# 300_PCB1.net
KiCad netlist of a schematic drawn in Altium Designer
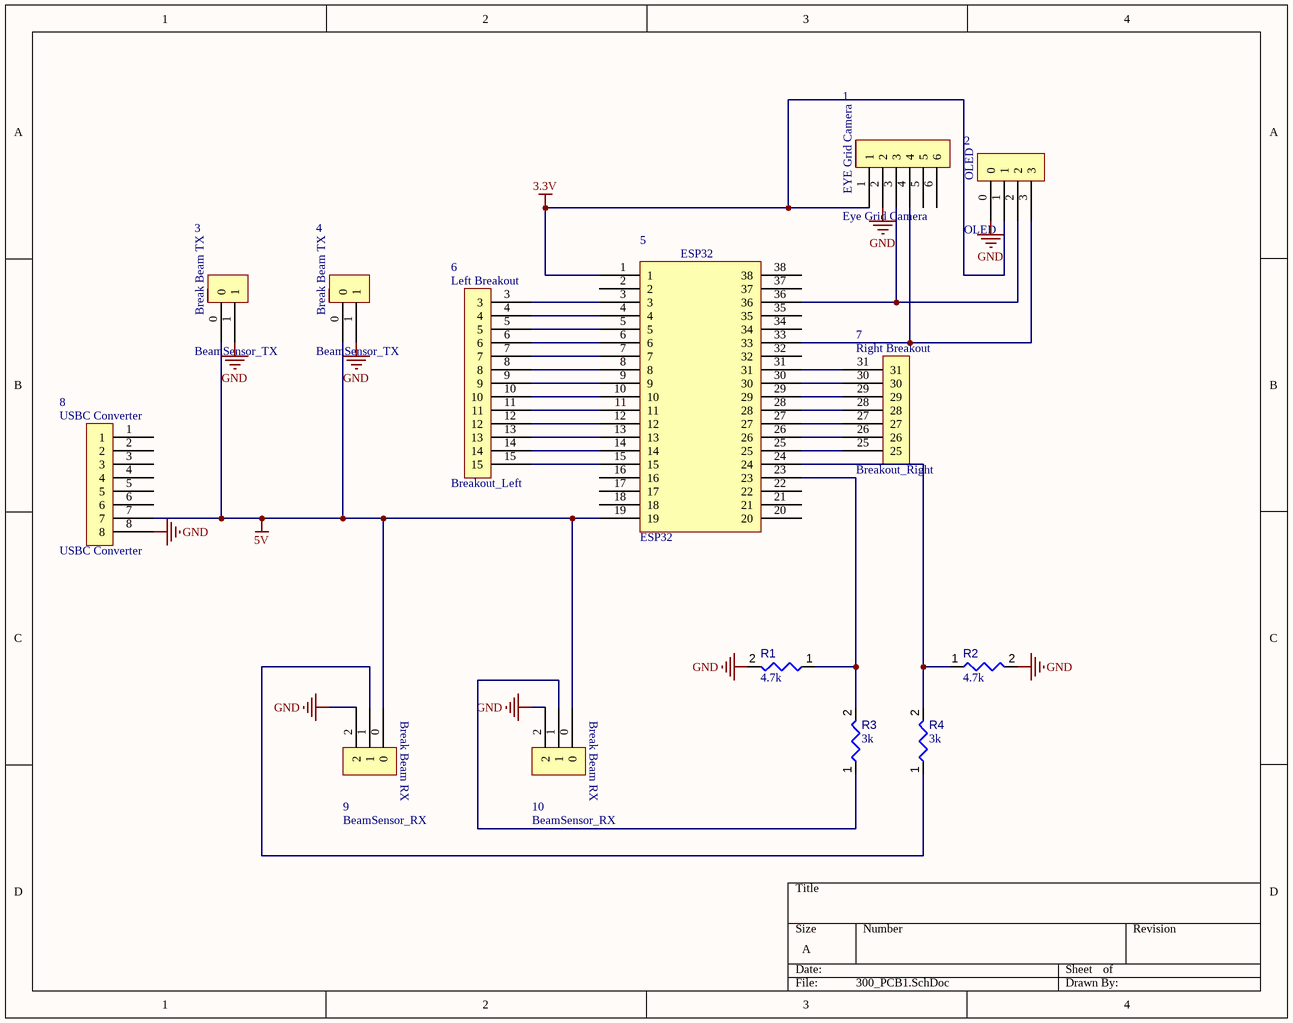
[diagram p0: 300_PCB1.SchDoc]

(export (version "E")
  (design (tool "Eeschema 10.0.6"))
  (components
    (comp (ref "1")
      (value "Eye Grid Camera")
      (footprint "IR Camera")
      (description "IR Camera")
      (libsource (lib "Jackson Stringfellow") (part "IR Camera"))
    )
    (comp (ref "2")
      (value "OLED")
      (footprint "OLED")
      (description "footprint of OLED display")
      (libsource (lib "Jackson Stringfellow") (part "OLED"))
    )
    (comp (ref "3")
      (value "BeamSensor_TX")
      (footprint "Beam_TX")
      (description "pinout for the break beam sensor")
      (libsource (lib "Jackson Stringfellow") (part "Beam_TX"))
    )
    (comp (ref "4")
      (value "BeamSensor_TX")
      (footprint "Beam_TX")
      (description "pinout for the break beam sensor")
      (libsource (lib "Jackson Stringfellow") (part "Beam_TX"))
    )
    (comp (ref "5")
      (value "ESP32")
      (footprint "ESP32")
      (description "first esp32 footprint")
      (libsource (lib "Jackson Stringfellow") (part "ESP32_sym"))
    )
    (comp (ref "6")
      (value "Breakout_Left")
      (footprint "Left Breakout")
      (description "left breakout rail")
      (libsource (lib "Jackson Stringfellow") (part "Breakout_Left"))
    )
    (comp (ref "7")
      (value "Breakout_Right")
      (footprint "Breakout_Right")
      (description "right breakout rail")
      (libsource (lib "Jackson Stringfellow") (part "Breakout_Right"))
    )
    (comp (ref "8")
      (value "USBC Converter")
      (footprint "USBC converter")
      (description "Converter for the power bank")
      (libsource (lib "Jackson Stringfellow") (part "USBC Converter"))
    )
    (comp (ref "9")
      (value "BeamSensor_RX")
      (footprint "Beam_RX")
      (description "pinout for the break beam sensor RX")
      (libsource (lib "Jackson Stringfellow") (part "Beam_RX"))
    )
    (comp (ref "10")
      (value "BeamSensor_RX")
      (footprint "Beam_RX")
      (description "pinout for the break beam sensor RX")
      (libsource (lib "Jackson Stringfellow") (part "Beam_RX"))
    )
    (comp (ref "R1")
      (value "4.7k")
      (footprint "RESC0402(1005)_L")
      (description "4K7 0.063W 1% 0402 (1005 Metric)  SMD")
      (fields (field (name "TOLERANCE") "1%") (field (name "POWER") "63mW"))
      (libsource (lib "EECS_300_PCB1") (part "CMP-009-00105-2"))
    )
    (comp (ref "R2")
      (value "4.7k")
      (footprint "RESC0402(1005)_L")
      (description "4K7 0.063W 1% 0402 (1005 Metric)  SMD")
      (fields (field (name "TOLERANCE") "1%") (field (name "POWER") "63mW"))
      (libsource (lib "EECS_300_PCB1") (part "CMP-009-00105-2"))
    )
    (comp (ref "R3")
      (value "3k")
      (footprint "RESC0402(1005)_L")
      (description "3K 0.063W 1% 0402 (1005 Metric)  SMD")
      (fields (field (name "POWER") "63mW") (field (name "TOLERANCE") "1%"))
      (libsource (lib "EECS_300_PCB1") (part "CMP-009-00099-2"))
    )
    (comp (ref "R4")
      (value "3k")
      (footprint "RESC0402(1005)_L")
      (description "3K 0.063W 1% 0402 (1005 Metric)  SMD")
      (fields (field (name "POWER") "63mW") (field (name "TOLERANCE") "1%"))
      (libsource (lib "EECS_300_PCB1") (part "CMP-009-00099-2"))
    )
  )
  (nets
    (net (code "1") (name "3.3V") (class "Default")
      (node (ref "1") (pin "1") (pinfunction "1_1") (pintype "passive"))
      (node (ref "2") (pin "1") (pinfunction "1_1") (pintype "passive"))
      (node (ref "5") (pin "1") (pinfunction "1_1") (pintype "passive"))
    )
    (net (code "2") (name "5V") (class "Default")
      (node (ref "10") (pin "0") (pinfunction "0_0") (pintype "passive"))
      (node (ref "3") (pin "0") (pinfunction "0_0") (pintype "passive"))
      (node (ref "4") (pin "0") (pinfunction "0_0") (pintype "passive"))
      (node (ref "5") (pin "19") (pinfunction "19_19") (pintype "passive"))
      (node (ref "8") (pin "7") (pinfunction "7_7") (pintype "passive"))
      (node (ref "9") (pin "0") (pinfunction "0_0") (pintype "passive"))
    )
    (net (code "3") (name "GND") (class "Default")
      (node (ref "1") (pin "2") (pinfunction "2_2") (pintype "passive"))
      (node (ref "10") (pin "2") (pinfunction "2_2") (pintype "passive"))
      (node (ref "2") (pin "0") (pinfunction "0_0") (pintype "passive"))
      (node (ref "3") (pin "1") (pinfunction "1_1") (pintype "passive"))
      (node (ref "4") (pin "1") (pinfunction "1_1") (pintype "passive"))
      (node (ref "8") (pin "8") (pinfunction "8_8") (pintype "passive"))
      (node (ref "9") (pin "2") (pinfunction "2_2") (pintype "passive"))
      (node (ref "R1") (pin "2") (pinfunction "2_2") (pintype "passive"))
      (node (ref "R2") (pin "2") (pinfunction "2_2") (pintype "passive"))
    )
    (net (code "4") (name "Net-(1-Pad3)") (class "Default")
      (node (ref "1") (pin "3") (pinfunction "3_3") (pintype "passive"))
      (node (ref "2") (pin "2") (pinfunction "2_2") (pintype "passive"))
      (node (ref "5") (pin "36") (pinfunction "36_36") (pintype "passive"))
    )
    (net (code "5") (name "Net-(1-Pad4)") (class "Default")
      (node (ref "1") (pin "4") (pinfunction "4_4") (pintype "passive"))
      (node (ref "2") (pin "3") (pinfunction "3_3") (pintype "passive"))
      (node (ref "5") (pin "33") (pinfunction "33_33") (pintype "passive"))
    )
    (net (code "6") (name "Net-(5-Pad3)") (class "Default")
      (node (ref "5") (pin "3") (pinfunction "3_3") (pintype "passive"))
      (node (ref "6") (pin "3") (pinfunction "3_3") (pintype "passive"))
    )
    (net (code "7") (name "Net-(5-Pad4)") (class "Default")
      (node (ref "5") (pin "4") (pinfunction "4_4") (pintype "passive"))
      (node (ref "6") (pin "4") (pinfunction "4_4") (pintype "passive"))
    )
    (net (code "8") (name "Net-(5-Pad5)") (class "Default")
      (node (ref "5") (pin "5") (pinfunction "5_5") (pintype "passive"))
      (node (ref "6") (pin "5") (pinfunction "5_5") (pintype "passive"))
    )
    (net (code "9") (name "Net-(5-Pad6)") (class "Default")
      (node (ref "5") (pin "6") (pinfunction "6_6") (pintype "passive"))
      (node (ref "6") (pin "6") (pinfunction "6_6") (pintype "passive"))
    )
    (net (code "10") (name "Net-(5-Pad7)") (class "Default")
      (node (ref "5") (pin "7") (pinfunction "7_7") (pintype "passive"))
      (node (ref "6") (pin "7") (pinfunction "7_7") (pintype "passive"))
    )
    (net (code "11") (name "Net-(5-Pad8)") (class "Default")
      (node (ref "5") (pin "8") (pinfunction "8_8") (pintype "passive"))
      (node (ref "6") (pin "8") (pinfunction "8_8") (pintype "passive"))
    )
    (net (code "12") (name "Net-(5-Pad9)") (class "Default")
      (node (ref "5") (pin "9") (pinfunction "9_9") (pintype "passive"))
      (node (ref "6") (pin "9") (pinfunction "9_9") (pintype "passive"))
    )
    (net (code "13") (name "Net-(5-Pad10)") (class "Default")
      (node (ref "5") (pin "10") (pinfunction "10_10") (pintype "passive"))
      (node (ref "6") (pin "10") (pinfunction "10_10") (pintype "passive"))
    )
    (net (code "14") (name "Net-(5-Pad11)") (class "Default")
      (node (ref "5") (pin "11") (pinfunction "11_11") (pintype "passive"))
      (node (ref "6") (pin "11") (pinfunction "11_11") (pintype "passive"))
    )
    (net (code "15") (name "Net-(5-Pad12)") (class "Default")
      (node (ref "5") (pin "12") (pinfunction "12_12") (pintype "passive"))
      (node (ref "6") (pin "12") (pinfunction "12_12") (pintype "passive"))
    )
    (net (code "16") (name "Net-(5-Pad13)") (class "Default")
      (node (ref "5") (pin "13") (pinfunction "13_13") (pintype "passive"))
      (node (ref "6") (pin "13") (pinfunction "13_13") (pintype "passive"))
    )
    (net (code "17") (name "Net-(5-Pad14)") (class "Default")
      (node (ref "5") (pin "14") (pinfunction "14_14") (pintype "passive"))
      (node (ref "6") (pin "14") (pinfunction "14_14") (pintype "passive"))
    )
    (net (code "18") (name "Net-(5-Pad15)") (class "Default")
      (node (ref "5") (pin "15") (pinfunction "15_15") (pintype "passive"))
      (node (ref "6") (pin "15") (pinfunction "15_15") (pintype "passive"))
    )
    (net (code "19") (name "Net-(5-Pad23)") (class "Default")
      (node (ref "5") (pin "23") (pinfunction "23_23") (pintype "passive"))
      (node (ref "R1") (pin "1") (pinfunction "1_1") (pintype "passive"))
      (node (ref "R3") (pin "2") (pinfunction "2_2") (pintype "passive"))
    )
    (net (code "20") (name "Net-(5-Pad24)") (class "Default")
      (node (ref "5") (pin "24") (pinfunction "24_24") (pintype "passive"))
      (node (ref "R2") (pin "1") (pinfunction "1_1") (pintype "passive"))
      (node (ref "R4") (pin "2") (pinfunction "2_2") (pintype "passive"))
    )
    (net (code "21") (name "Net-(5-Pad25)") (class "Default")
      (node (ref "5") (pin "25") (pinfunction "25_25") (pintype "passive"))
      (node (ref "7") (pin "25") (pinfunction "25_25") (pintype "passive"))
    )
    (net (code "22") (name "Net-(5-Pad26)") (class "Default")
      (node (ref "5") (pin "26") (pinfunction "26_26") (pintype "passive"))
      (node (ref "7") (pin "26") (pinfunction "26_26") (pintype "passive"))
    )
    (net (code "23") (name "Net-(5-Pad27)") (class "Default")
      (node (ref "5") (pin "27") (pinfunction "27_27") (pintype "passive"))
      (node (ref "7") (pin "27") (pinfunction "27_27") (pintype "passive"))
    )
    (net (code "24") (name "Net-(5-Pad28)") (class "Default")
      (node (ref "5") (pin "28") (pinfunction "28_28") (pintype "passive"))
      (node (ref "7") (pin "28") (pinfunction "28_28") (pintype "passive"))
    )
    (net (code "25") (name "Net-(5-Pad29)") (class "Default")
      (node (ref "5") (pin "29") (pinfunction "29_29") (pintype "passive"))
      (node (ref "7") (pin "29") (pinfunction "29_29") (pintype "passive"))
    )
    (net (code "26") (name "Net-(5-Pad30)") (class "Default")
      (node (ref "5") (pin "30") (pinfunction "30_30") (pintype "passive"))
      (node (ref "7") (pin "30") (pinfunction "30_30") (pintype "passive"))
    )
    (net (code "27") (name "Net-(5-Pad31)") (class "Default")
      (node (ref "5") (pin "31") (pinfunction "31_31") (pintype "passive"))
      (node (ref "7") (pin "31") (pinfunction "31_31") (pintype "passive"))
    )
    (net (code "28") (name "Net-(9-Pad1)") (class "Default")
      (node (ref "9") (pin "1") (pinfunction "1_1") (pintype "passive"))
      (node (ref "R4") (pin "1") (pinfunction "1_1") (pintype "passive"))
    )
    (net (code "29") (name "Net-(10-Pad1)") (class "Default")
      (node (ref "10") (pin "1") (pinfunction "1_1") (pintype "passive"))
      (node (ref "R3") (pin "1") (pinfunction "1_1") (pintype "passive"))
    )
    (net (code "30") (name "unconnected-(1-Pad5)") (class "Default")
      (node (ref "1") (pin "5") (pinfunction "5_5") (pintype "passive"))
    )
    (net (code "31") (name "unconnected-(1-Pad6)") (class "Default")
      (node (ref "1") (pin "6") (pinfunction "6_6") (pintype "passive"))
    )
    (net (code "32") (name "unconnected-(5-Pad2)") (class "Default")
      (node (ref "5") (pin "2") (pinfunction "2_2") (pintype "passive"))
    )
    (net (code "33") (name "unconnected-(5-Pad16)") (class "Default")
      (node (ref "5") (pin "16") (pinfunction "16_16") (pintype "passive"))
    )
    (net (code "34") (name "unconnected-(5-Pad17)") (class "Default")
      (node (ref "5") (pin "17") (pinfunction "17_17") (pintype "passive"))
    )
    (net (code "35") (name "unconnected-(5-Pad18)") (class "Default")
      (node (ref "5") (pin "18") (pinfunction "18_18") (pintype "passive"))
    )
    (net (code "36") (name "unconnected-(5-Pad20)") (class "Default")
      (node (ref "5") (pin "20") (pinfunction "20_20") (pintype "passive"))
    )
    (net (code "37") (name "unconnected-(5-Pad21)") (class "Default")
      (node (ref "5") (pin "21") (pinfunction "21_21") (pintype "passive"))
    )
    (net (code "38") (name "unconnected-(5-Pad22)") (class "Default")
      (node (ref "5") (pin "22") (pinfunction "22_22") (pintype "passive"))
    )
    (net (code "39") (name "unconnected-(5-Pad32)") (class "Default")
      (node (ref "5") (pin "32") (pinfunction "32_32") (pintype "passive"))
    )
    (net (code "40") (name "unconnected-(5-Pad34)") (class "Default")
      (node (ref "5") (pin "34") (pinfunction "34_34") (pintype "passive"))
    )
    (net (code "41") (name "unconnected-(5-Pad35)") (class "Default")
      (node (ref "5") (pin "35") (pinfunction "35_35") (pintype "passive"))
    )
    (net (code "42") (name "unconnected-(5-Pad37)") (class "Default")
      (node (ref "5") (pin "37") (pinfunction "37_37") (pintype "passive"))
    )
    (net (code "43") (name "unconnected-(5-Pad38)") (class "Default")
      (node (ref "5") (pin "38") (pinfunction "38_38") (pintype "passive"))
    )
    (net (code "44") (name "unconnected-(8-Pad1)") (class "Default")
      (node (ref "8") (pin "1") (pinfunction "1_1") (pintype "passive"))
    )
    (net (code "45") (name "unconnected-(8-Pad2)") (class "Default")
      (node (ref "8") (pin "2") (pinfunction "2_2") (pintype "passive"))
    )
    (net (code "46") (name "unconnected-(8-Pad3)") (class "Default")
      (node (ref "8") (pin "3") (pinfunction "3_3") (pintype "passive"))
    )
    (net (code "47") (name "unconnected-(8-Pad4)") (class "Default")
      (node (ref "8") (pin "4") (pinfunction "4_4") (pintype "passive"))
    )
    (net (code "48") (name "unconnected-(8-Pad5)") (class "Default")
      (node (ref "8") (pin "5") (pinfunction "5_5") (pintype "passive"))
    )
    (net (code "49") (name "unconnected-(8-Pad6)") (class "Default")
      (node (ref "8") (pin "6") (pinfunction "6_6") (pintype "passive"))
    )
  )
)
